# accel_mag.net
KiCad netlist of a schematic drawn in Altium Designer
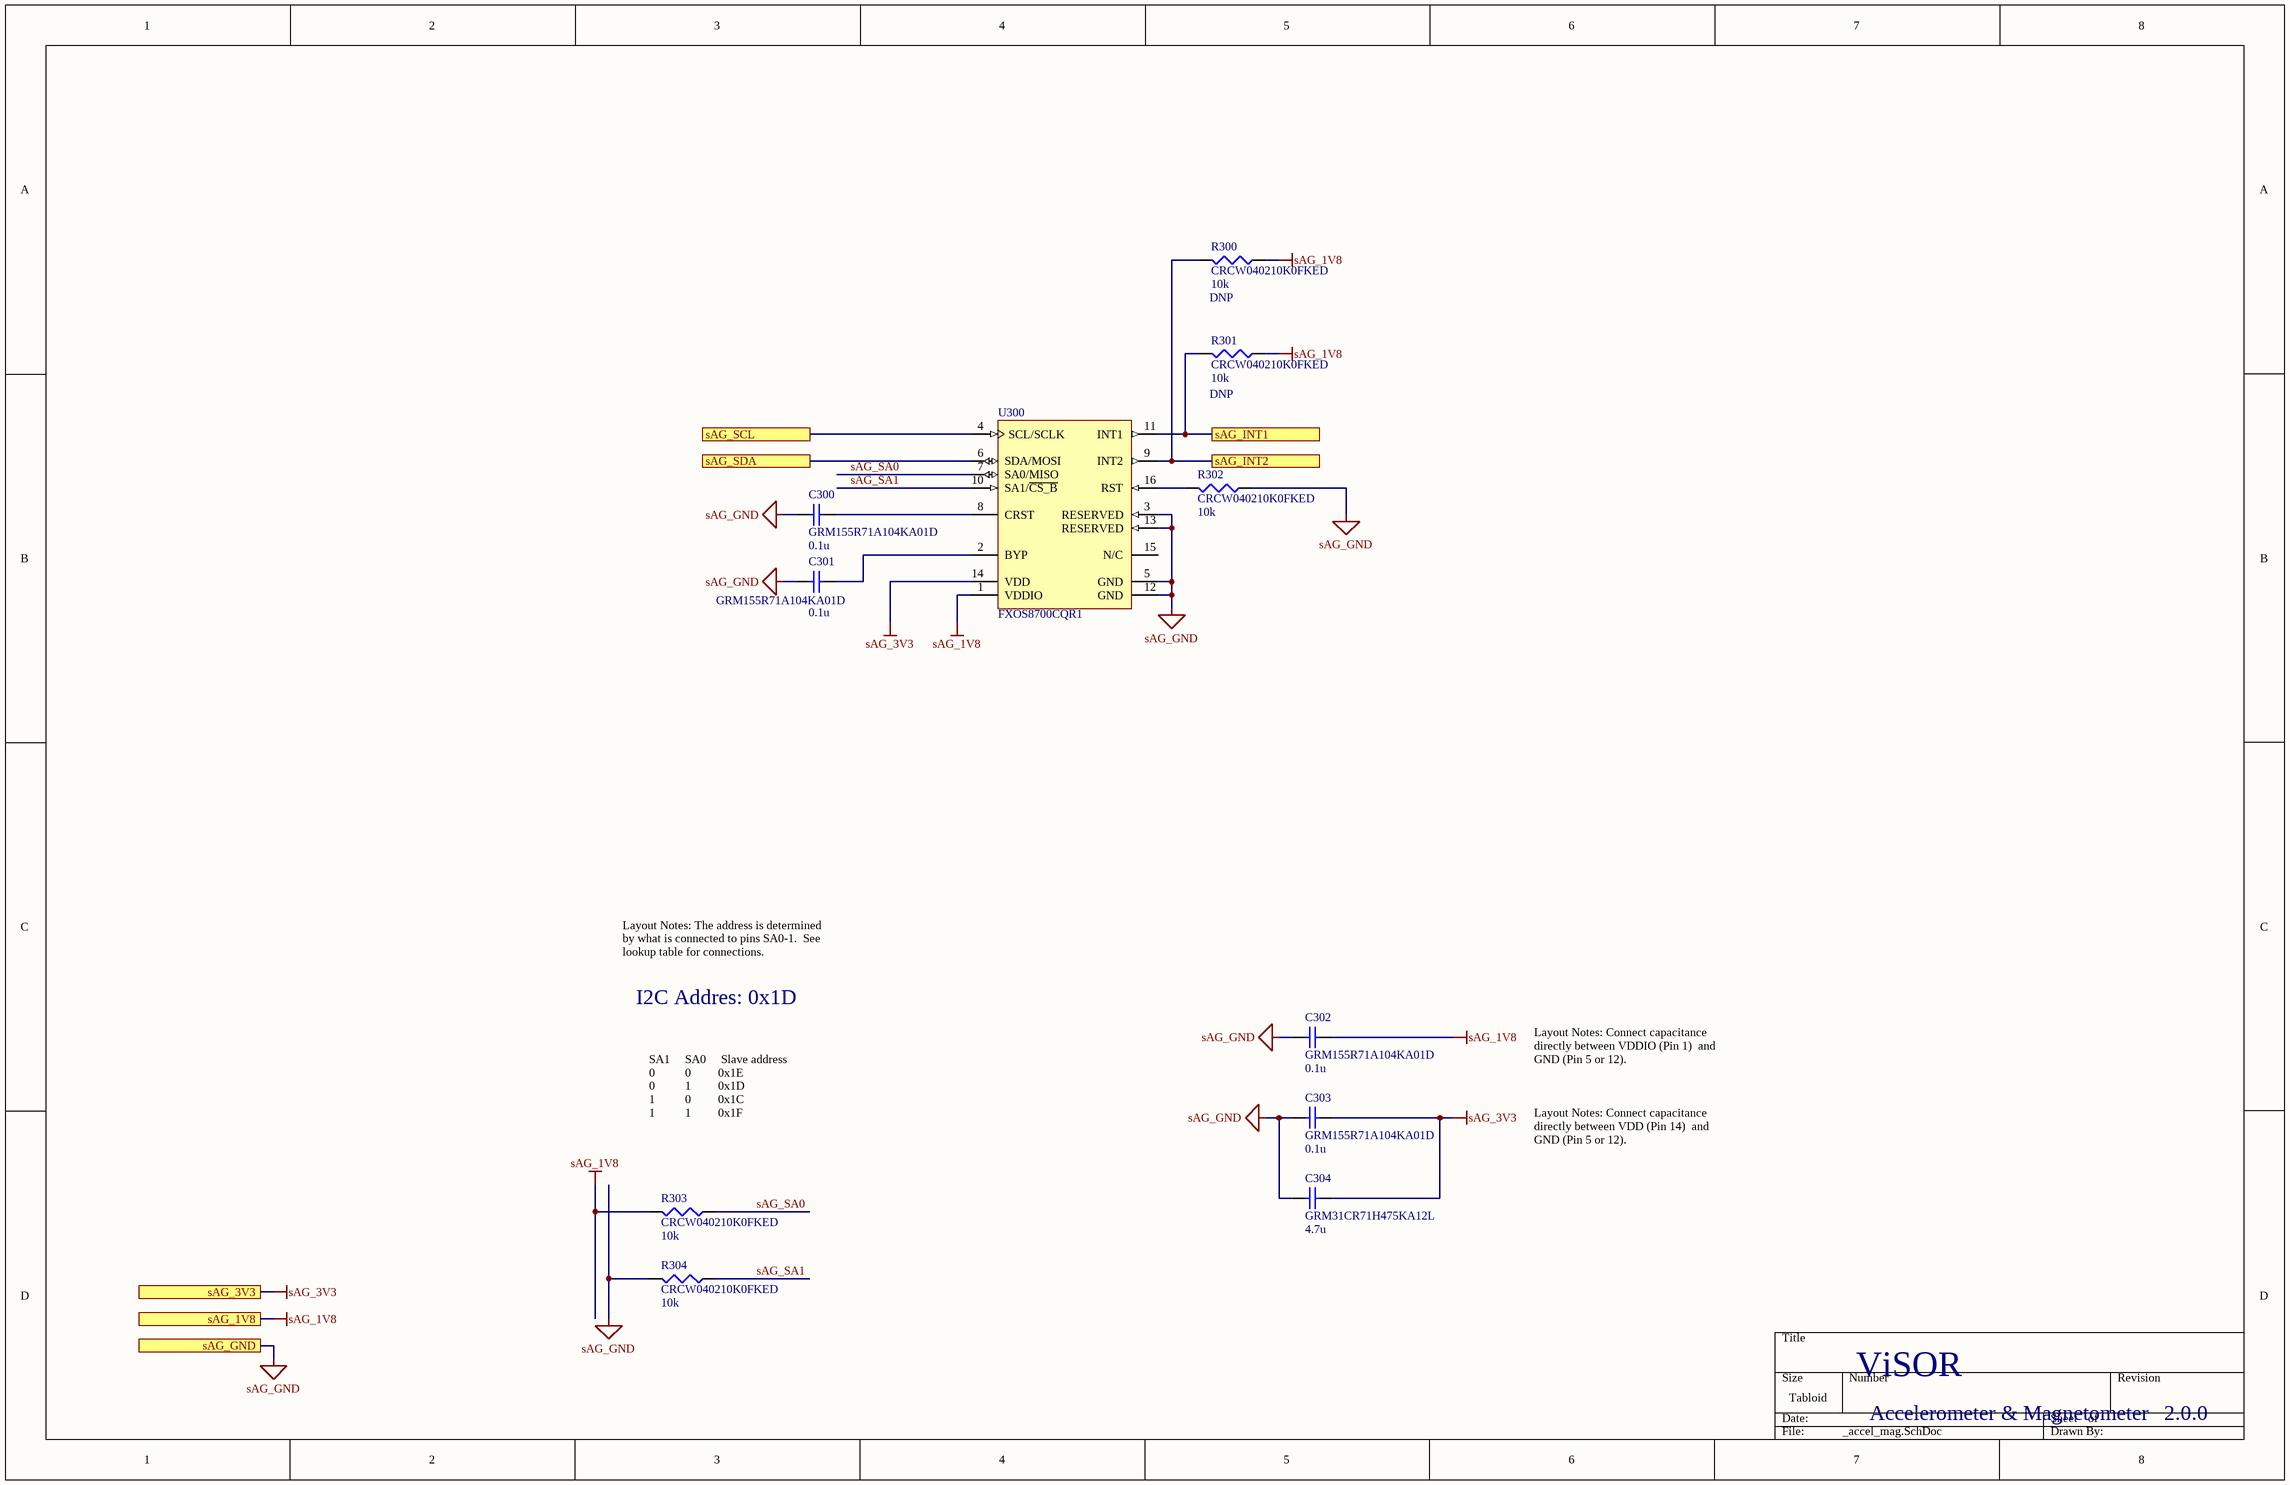
[diagram p0: _accel_mag.SchDoc]

(export (version "E")
  (design (tool "Eeschema 10.0.6"))
  (components
    (comp (ref "C300")
      (value "GRM155R71A104KA01D")
      (footprint "0402")
      (description "-55-125C, 1005, 10V, X7R, ±10%")
      (fields (field (name "ALTIUM_VALUE") "0.1u"))
      (libsource (lib "standard_capacitors") (part "GRM155R71AxxxKdddd"))
    )
    (comp (ref "C301")
      (value "GRM155R71A104KA01D")
      (footprint "0402")
      (description "-55-125C, 1005, 10V, X7R, ±10%")
      (fields (field (name "ALTIUM_VALUE") "0.1u"))
      (libsource (lib "standard_capacitors") (part "GRM155R71AxxxKdddd"))
    )
    (comp (ref "C302")
      (value "GRM155R71A104KA01D")
      (footprint "0402")
      (description "-55-125C, 1005, 10V, X7R, ±10%")
      (fields (field (name "ALTIUM_VALUE") "0.1u"))
      (libsource (lib "standard_capacitors") (part "GRM155R71AxxxKdddd"))
    )
    (comp (ref "C303")
      (value "GRM155R71A104KA01D")
      (footprint "0402")
      (description "-55-125C, 1005, 10V, X7R, ±10%")
      (fields (field (name "ALTIUM_VALUE") "0.1u"))
      (libsource (lib "standard_capacitors") (part "GRM155R71AxxxKdddd"))
    )
    (comp (ref "C304")
      (value "GRM31CR71H475KA12L")
      (footprint "1206")
      (description "-55-125C, 3216, 50V, X7R, ±10%")
      (fields (field (name "ALTIUM_VALUE") "4.7u"))
      (libsource (lib "standard_capacitors") (part "GRM31CR71HxxxKdddd"))
    )
    (comp (ref "R300")
      (value "CRCW040210K0FKED")
      (footprint "0402")
      (description "0.125W, -55-155C, 1005, 50V, ±1%")
      (fields (field (name "ALTIUM_UNNAMED_1") "DNP") (field (name "ALTIUM_VALUE") "10k"))
      (libsource (lib "standard_resistors") (part "CRCW0402xxxxFKED"))
    )
    (comp (ref "R301")
      (value "CRCW040210K0FKED")
      (footprint "0402")
      (description "0.125W, -55-155C, 1005, 50V, ±1%")
      (fields (field (name "ALTIUM_UNNAMED_1") "DNP") (field (name "ALTIUM_VALUE") "10k"))
      (libsource (lib "standard_resistors") (part "CRCW0402xxxxFKED"))
    )
    (comp (ref "R302")
      (value "CRCW040210K0FKED")
      (footprint "0402")
      (description "0.125W, -55-155C, 1005, 50V, ±1%")
      (fields (field (name "ALTIUM_VALUE") "10k"))
      (libsource (lib "standard_resistors") (part "CRCW0402xxxxFKED"))
    )
    (comp (ref "R303")
      (value "CRCW040210K0FKED")
      (footprint "0402")
      (description "0.125W, -55-155C, 1005, 50V, ±1%")
      (fields (field (name "ALTIUM_VALUE") "10k"))
      (libsource (lib "standard_resistors") (part "CRCW0402xxxxFKED"))
    )
    (comp (ref "R304")
      (value "CRCW040210K0FKED")
      (footprint "0402")
      (description "0.125W, -55-155C, 1005, 50V, ±1%")
      (fields (field (name "ALTIUM_VALUE") "10k"))
      (libsource (lib "standard_resistors") (part "CRCW0402xxxxFKED"))
    )
    (comp (ref "U300")
      (value "FXOS8700CQR1")
      (footprint "FREE-QFN-16-3000X3000DE_V")
      (fields (field (name "MANUFACTURER") "Freescale"))
      (libsource (lib "Altium Content Vault") (part "FREE-FXOS8700CQR1-16"))
    )
  )
  (nets
    (net (code "1") (name "/sAG_INT1") (class "Default")
      (node (ref "R301") (pin "2") (pinfunction "2_2") (pintype "passive"))
      (node (ref "U300") (pin "11") (pinfunction "INT1_11") (pintype "output"))
    )
    (net (code "2") (name "/sAG_INT2") (class "Default")
      (node (ref "R300") (pin "2") (pinfunction "2_2") (pintype "passive"))
      (node (ref "U300") (pin "9") (pinfunction "INT2_9") (pintype "output"))
    )
    (net (code "3") (name "/sAG_SA0") (class "Default")
      (node (ref "R303") (pin "1") (pinfunction "1_1") (pintype "passive"))
      (node (ref "U300") (pin "7") (pinfunction "SA0/MISO_7") (pintype "bidirectional"))
    )
    (net (code "4") (name "/sAG_SA1") (class "Default")
      (node (ref "R304") (pin "1") (pinfunction "1_1") (pintype "passive"))
      (node (ref "U300") (pin "10") (pinfunction "SA1/~{CS_B}_10") (pintype "input"))
    )
    (net (code "5") (name "/sAG_SCL") (class "Default")
      (node (ref "U300") (pin "4") (pinfunction "SCL/SCLK_4") (pintype "input"))
    )
    (net (code "6") (name "/sAG_SDA") (class "Default")
      (node (ref "U300") (pin "6") (pinfunction "SDA/MOSI_6") (pintype "bidirectional"))
    )
    (net (code "7") (name "Net-(U300-BYP)") (class "Default")
      (node (ref "C301") (pin "1") (pinfunction "1_1") (pintype "passive"))
      (node (ref "U300") (pin "2") (pinfunction "BYP_2") (pintype "passive"))
    )
    (net (code "8") (name "Net-(U300-CRST)") (class "Default")
      (node (ref "C300") (pin "1") (pinfunction "1_1") (pintype "passive"))
      (node (ref "U300") (pin "8") (pinfunction "CRST_8") (pintype "passive"))
    )
    (net (code "9") (name "Net-(U300-RST)") (class "Default")
      (node (ref "R302") (pin "2") (pinfunction "2_2") (pintype "passive"))
      (node (ref "U300") (pin "16") (pinfunction "RST_16") (pintype "input"))
    )
    (net (code "10") (name "sAG_1V8") (class "Default")
      (node (ref "C302") (pin "2") (pinfunction "2_2") (pintype "passive"))
      (node (ref "R300") (pin "1") (pinfunction "1_1") (pintype "passive"))
      (node (ref "R301") (pin "1") (pinfunction "1_1") (pintype "passive"))
      (node (ref "R303") (pin "2") (pinfunction "2_2") (pintype "passive"))
      (node (ref "U300") (pin "1") (pinfunction "VDDIO_1") (pintype "power_in"))
    )
    (net (code "11") (name "sAG_3V3") (class "Default")
      (node (ref "C303") (pin "2") (pinfunction "2_2") (pintype "passive"))
      (node (ref "C304") (pin "2") (pinfunction "2_2") (pintype "passive"))
      (node (ref "U300") (pin "14") (pinfunction "VDD_14") (pintype "power_in"))
    )
    (net (code "12") (name "sAG_GND") (class "Default")
      (node (ref "C300") (pin "2") (pinfunction "2_2") (pintype "passive"))
      (node (ref "C301") (pin "2") (pinfunction "2_2") (pintype "passive"))
      (node (ref "C302") (pin "1") (pinfunction "1_1") (pintype "passive"))
      (node (ref "C303") (pin "1") (pinfunction "1_1") (pintype "passive"))
      (node (ref "C304") (pin "1") (pinfunction "1_1") (pintype "passive"))
      (node (ref "R302") (pin "1") (pinfunction "1_1") (pintype "passive"))
      (node (ref "R304") (pin "2") (pinfunction "2_2") (pintype "passive"))
      (node (ref "U300") (pin "12") (pinfunction "GND_12") (pintype "power_in"))
      (node (ref "U300") (pin "13") (pinfunction "RESERVED_13") (pintype "input"))
      (node (ref "U300") (pin "3") (pinfunction "RESERVED_3") (pintype "input"))
      (node (ref "U300") (pin "5") (pinfunction "GND_5") (pintype "power_in"))
    )
    (net (code "13") (name "unconnected-(U300-N{slash}C-Pad15)") (class "Default")
      (node (ref "U300") (pin "15") (pinfunction "N/C_15") (pintype "passive"))
    )
  )
)
